# 2021-01-12_HALO_Main_Board.net
KiCad netlist of a schematic drawn in EAGLE
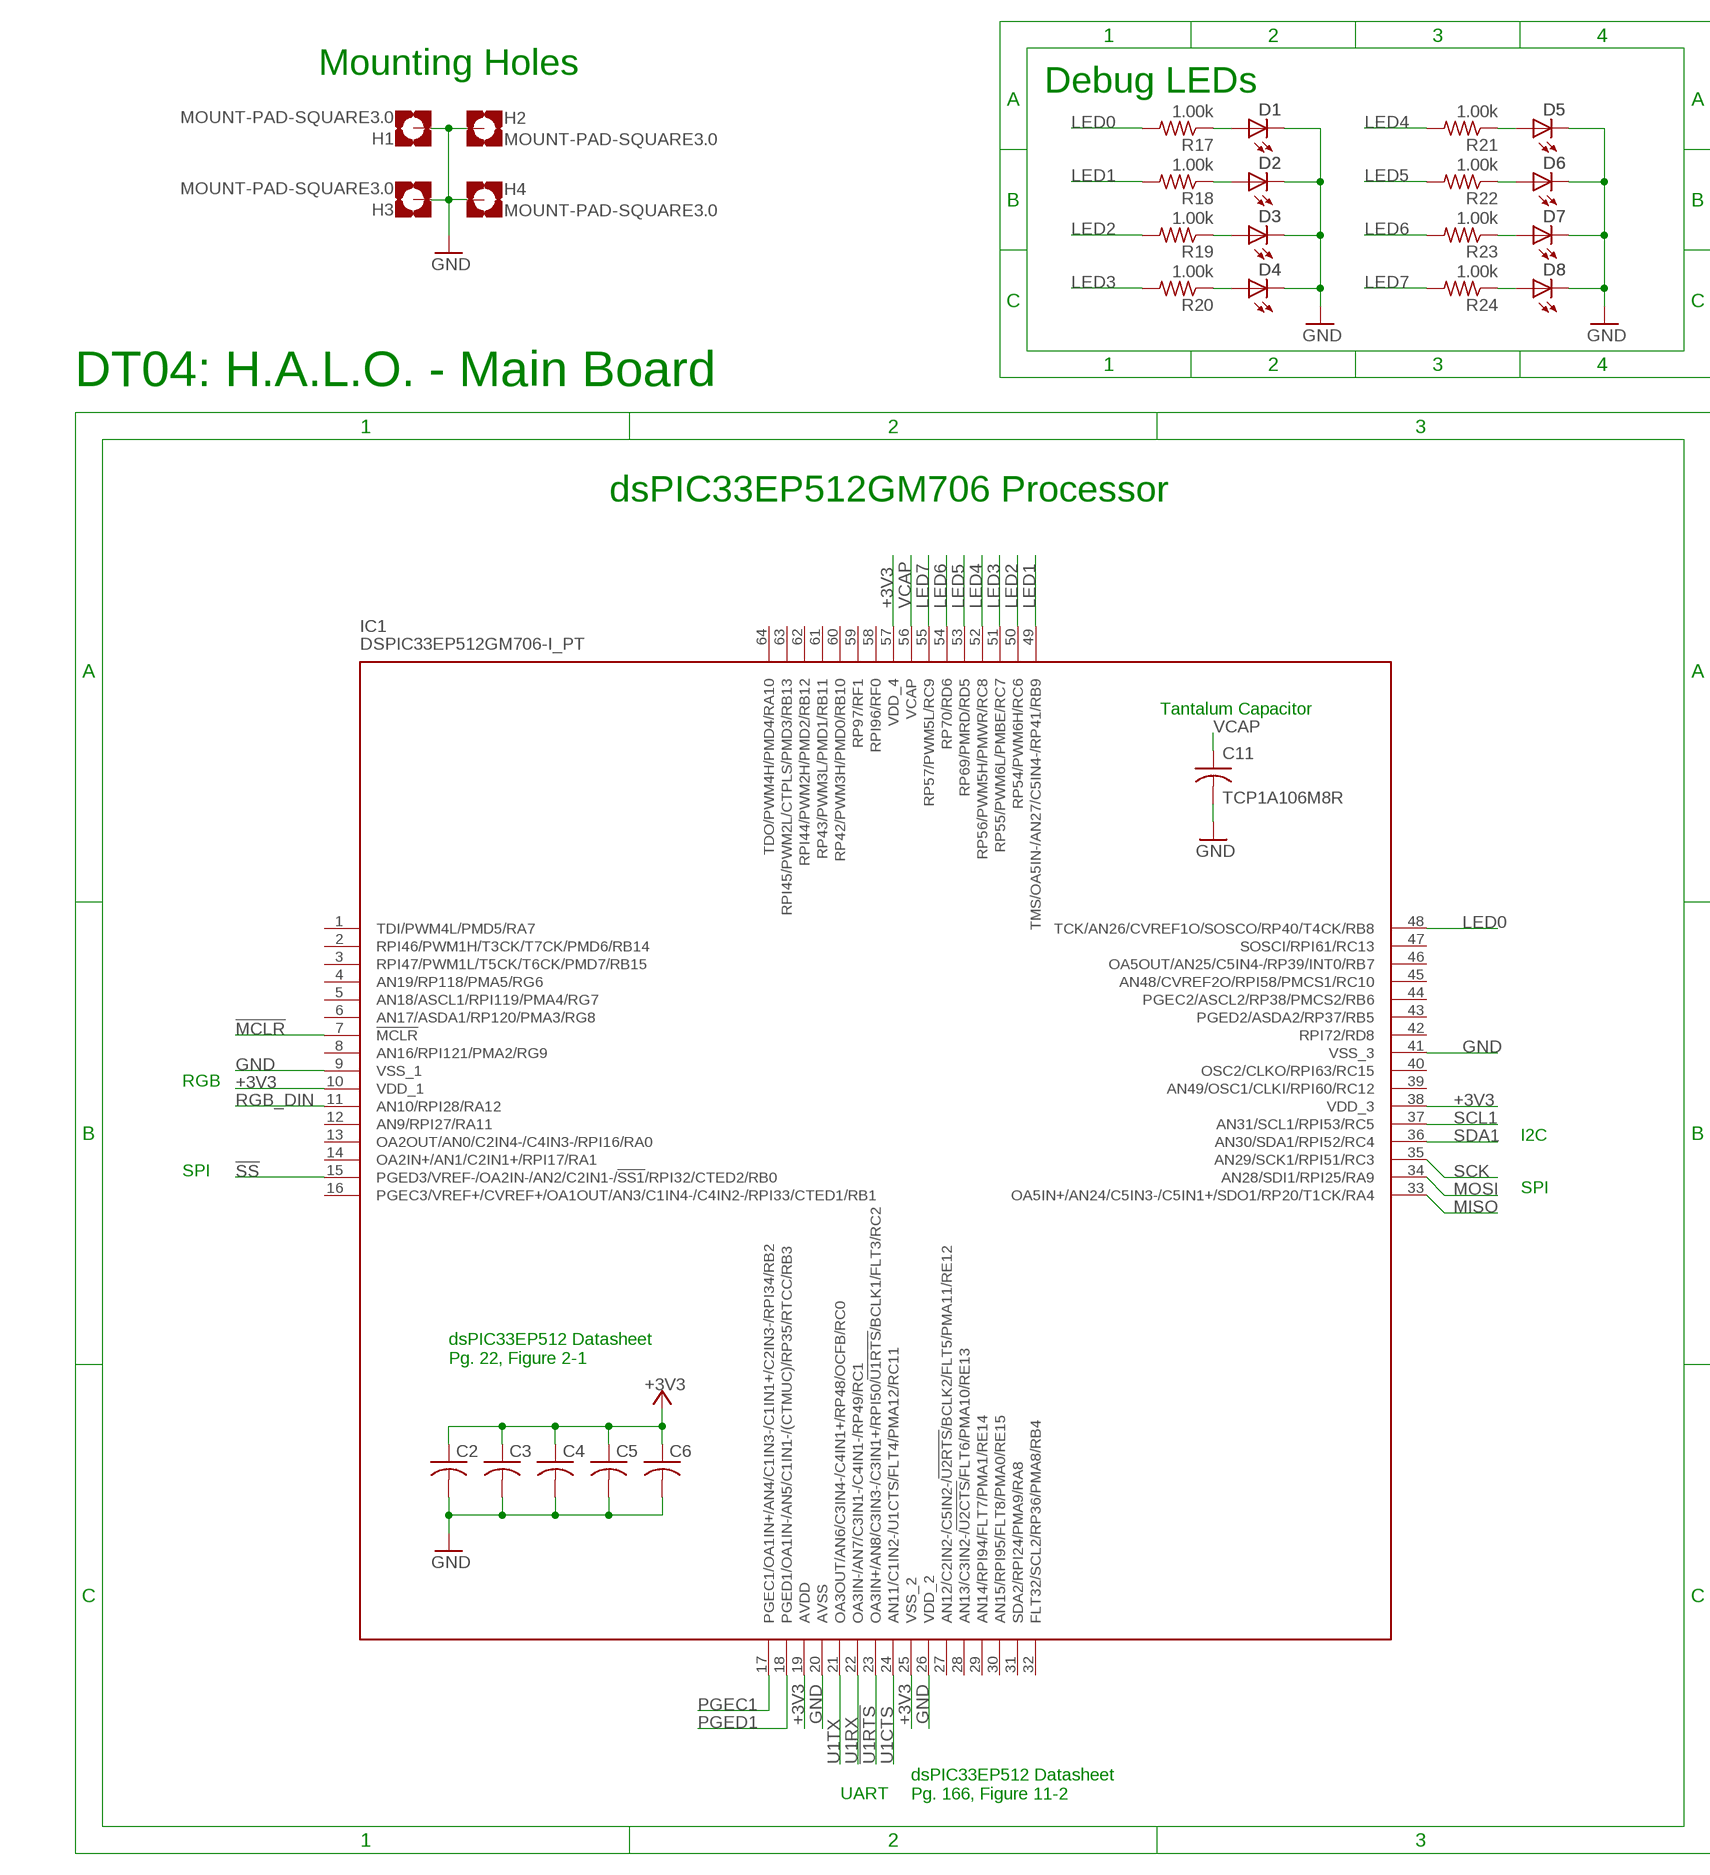
[diagram p0: schematic, sheet 1, part 1 of 2]
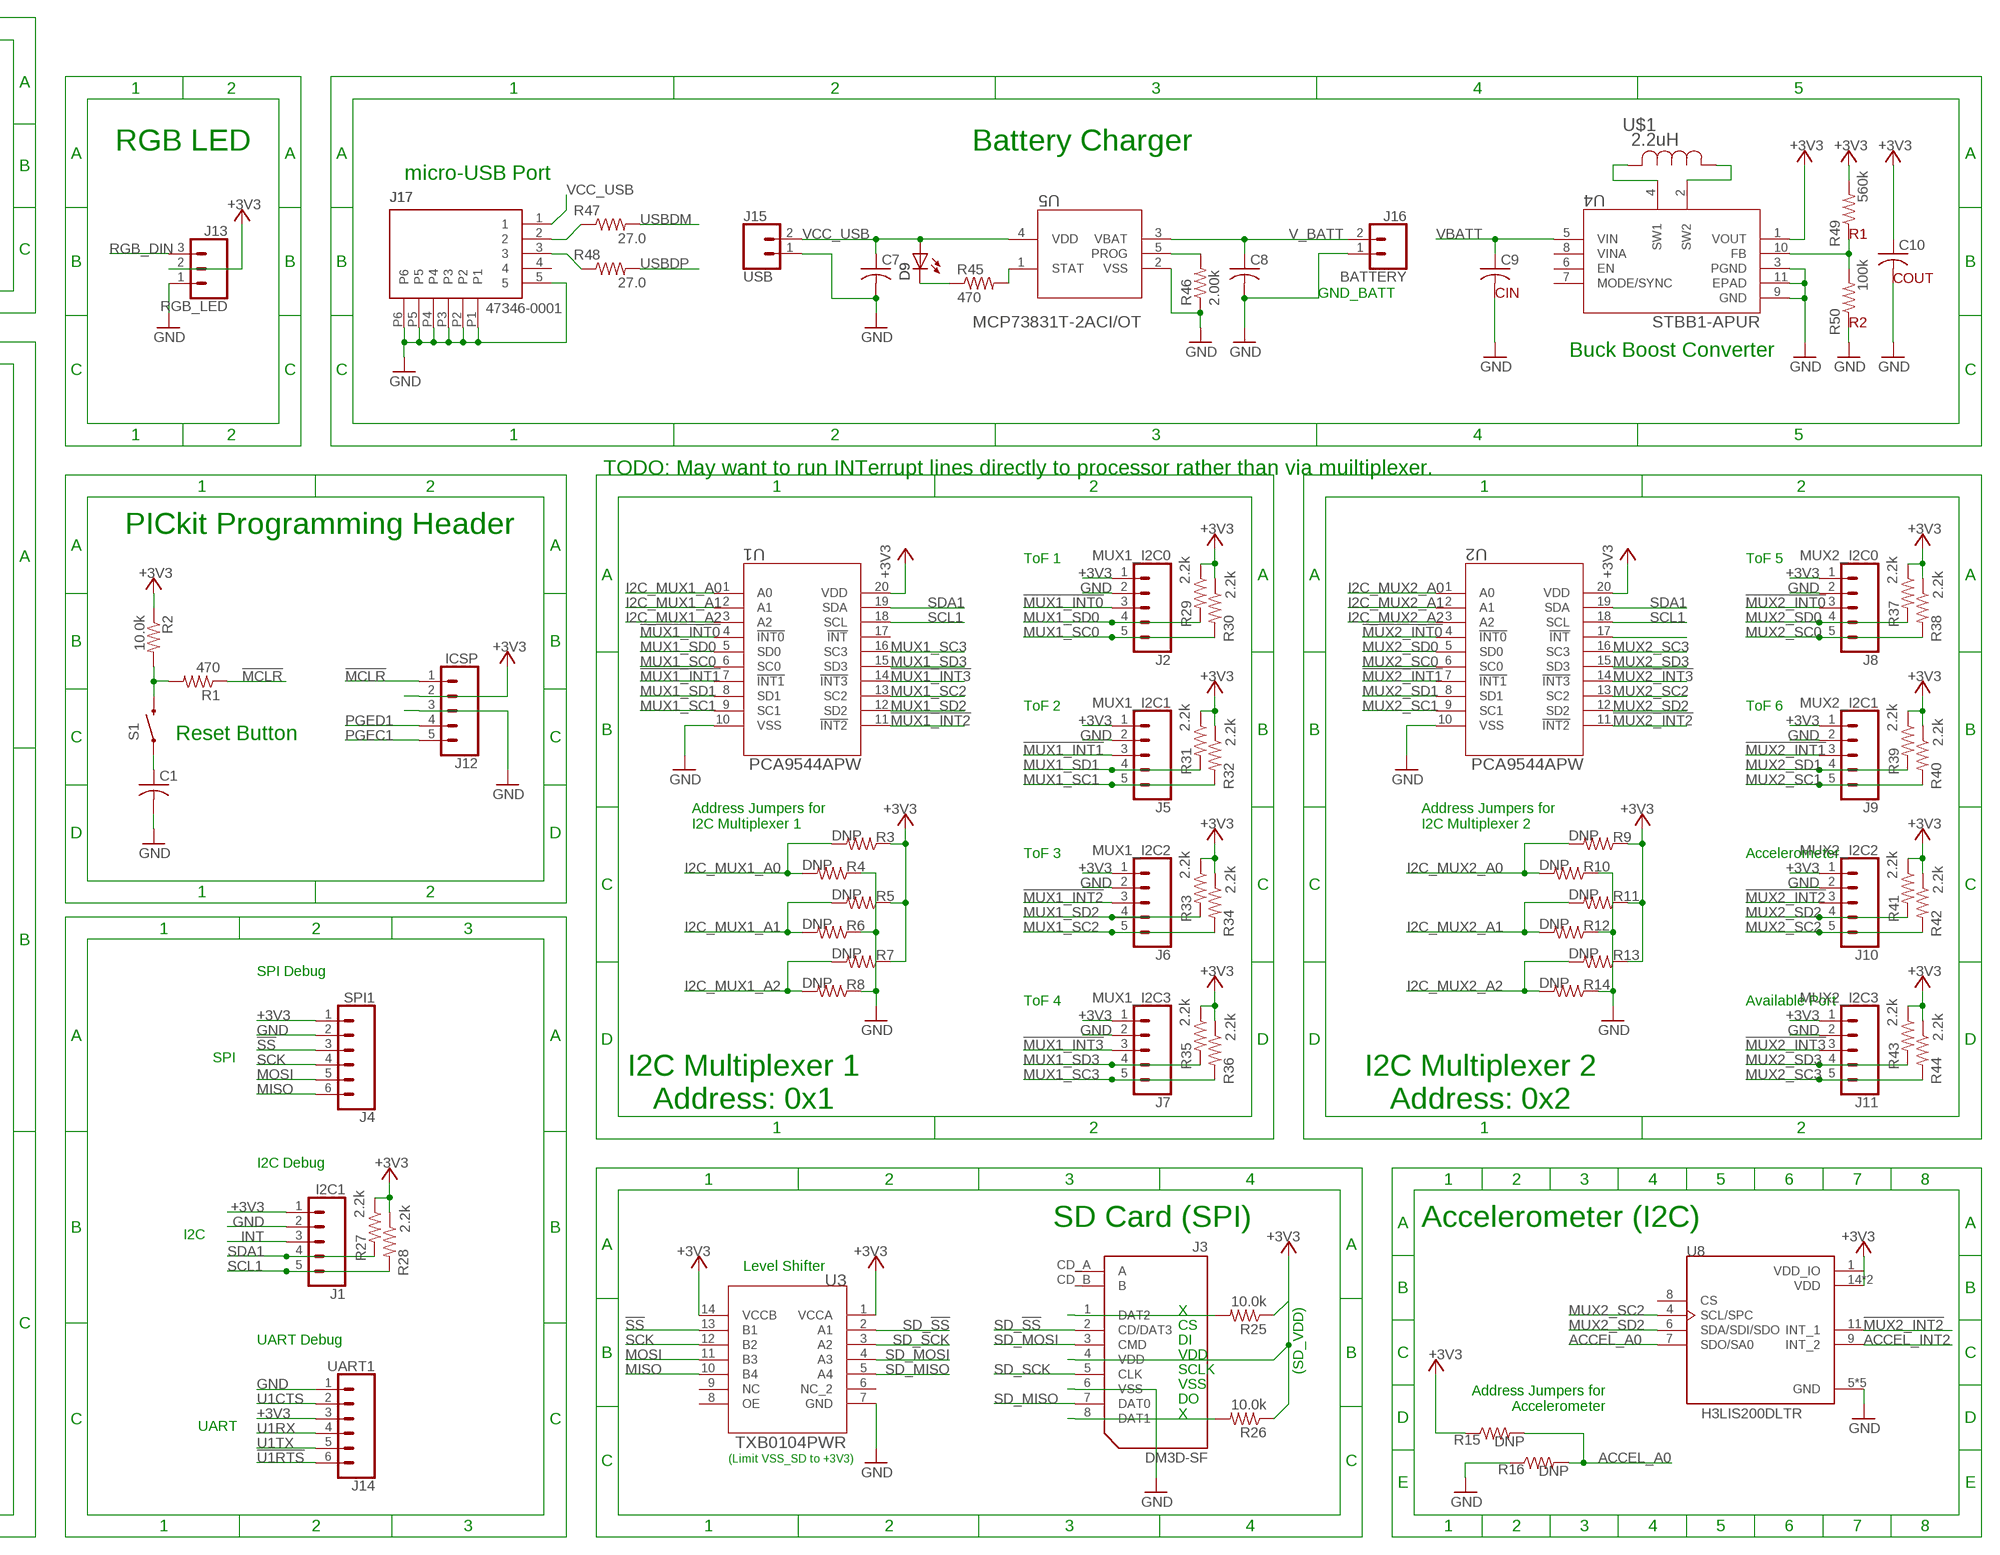
[diagram p1: schematic, sheet 1, part 2 of 2]

(export (version "E")
  (design (tool "Eeschema 10.0.6"))
  (components
    (comp (ref "C1")
      (value "0.1uF")
      (footprint "eagle-import:C0805")
      (libsource (lib "eagle-import") (part "C-USC0805"))
    )
    (comp (ref "C2")
      (value "0.1uF")
      (footprint "eagle-import:C0805")
      (libsource (lib "eagle-import") (part "C-USC0805"))
    )
    (comp (ref "C3")
      (value "0.1uF")
      (footprint "eagle-import:C0805")
      (libsource (lib "eagle-import") (part "C-USC0805"))
    )
    (comp (ref "C4")
      (value "0.1uF")
      (footprint "eagle-import:C0805")
      (libsource (lib "eagle-import") (part "C-USC0805"))
    )
    (comp (ref "C5")
      (value "0.1uF")
      (footprint "eagle-import:C0805")
      (libsource (lib "eagle-import") (part "C-USC0805"))
    )
    (comp (ref "C6")
      (value "0.1uF")
      (footprint "eagle-import:C0805")
      (libsource (lib "eagle-import") (part "C-USC0805"))
    )
    (comp (ref "C7")
      (value "4.7uF")
      (footprint "eagle-import:C0805")
      (libsource (lib "eagle-import") (part "C-USC0805"))
    )
    (comp (ref "C8")
      (value "4.7uF")
      (footprint "eagle-import:C0805")
      (libsource (lib "eagle-import") (part "C-USC0805"))
    )
    (comp (ref "C9")
      (value "10uF")
      (footprint "eagle-import:C0805")
      (libsource (lib "eagle-import") (part "C-USC0805"))
    )
    (comp (ref "C10")
      (value "22uF")
      (footprint "eagle-import:C0805")
      (libsource (lib "eagle-import") (part "C-USC0805"))
    )
    (comp (ref "C11")
      (value "TCP1A106M8R")
      (footprint "eagle-import:TCP_ROM")
      (libsource (lib "eagle-import") (part "TCP1A106M8R"))
    )
    (comp (ref "D1")
      (value "CHIP-LED0805")
      (footprint "eagle-import:CHIP-LED0805")
      (libsource (lib "eagle-import") (part "CHIP-LED0805"))
    )
    (comp (ref "D2")
      (value "CHIP-LED0805")
      (footprint "eagle-import:CHIP-LED0805")
      (libsource (lib "eagle-import") (part "CHIP-LED0805"))
    )
    (comp (ref "D3")
      (value "CHIP-LED0805")
      (footprint "eagle-import:CHIP-LED0805")
      (libsource (lib "eagle-import") (part "CHIP-LED0805"))
    )
    (comp (ref "D4")
      (value "CHIP-LED0805")
      (footprint "eagle-import:CHIP-LED0805")
      (libsource (lib "eagle-import") (part "CHIP-LED0805"))
    )
    (comp (ref "D5")
      (value "CHIP-LED0805")
      (footprint "eagle-import:CHIP-LED0805")
      (libsource (lib "eagle-import") (part "CHIP-LED0805"))
    )
    (comp (ref "D6")
      (value "CHIP-LED0805")
      (footprint "eagle-import:CHIP-LED0805")
      (libsource (lib "eagle-import") (part "CHIP-LED0805"))
    )
    (comp (ref "D7")
      (value "CHIP-LED0805")
      (footprint "eagle-import:CHIP-LED0805")
      (libsource (lib "eagle-import") (part "CHIP-LED0805"))
    )
    (comp (ref "D8")
      (value "CHIP-LED0805")
      (footprint "eagle-import:CHIP-LED0805")
      (libsource (lib "eagle-import") (part "CHIP-LED0805"))
    )
    (comp (ref "D9")
      (value "CHIP-LED0805")
      (footprint "eagle-import:CHIP-LED0805")
      (libsource (lib "eagle-import") (part "CHIP-LED0805"))
    )
    (comp (ref "H1")
      (value "MOUNT-PAD-SQUARE3.0")
      (footprint "eagle-import:3,0-PAD-SQUARE")
      (libsource (lib "eagle-import") (part "MOUNT-PAD-SQUARE3.0"))
    )
    (comp (ref "H2")
      (value "MOUNT-PAD-SQUARE3.0")
      (footprint "eagle-import:3,0-PAD-SQUARE")
      (libsource (lib "eagle-import") (part "MOUNT-PAD-SQUARE3.0"))
    )
    (comp (ref "H3")
      (value "MOUNT-PAD-SQUARE3.0")
      (footprint "eagle-import:3,0-PAD-SQUARE")
      (libsource (lib "eagle-import") (part "MOUNT-PAD-SQUARE3.0"))
    )
    (comp (ref "H4")
      (value "MOUNT-PAD-SQUARE3.0")
      (footprint "eagle-import:3,0-PAD-SQUARE")
      (libsource (lib "eagle-import") (part "MOUNT-PAD-SQUARE3.0"))
    )
    (comp (ref "IC1")
      (value "DSPIC33EP512GM706-I_PT")
      (footprint "eagle-import:QFP50P1200X1200X120-64N")
      (fields
        (field (name "ARROW_PART_NUMBER") "DSPIC33EP512GM706-I/PT")
        (field (name "MOUSER_PART_NUMBER") "579-512GM706-I/PT")
      )
      (libsource (lib "eagle-import") (part "DSPIC33EP512GM706-I_PT"))
    )
    (comp (ref "J1")
      (value "I2C1")
      (footprint "eagle-import:1X05")
      (libsource (lib "eagle-import") (part "CONN_05"))
    )
    (comp (ref "J2")
      (value "MUX1_I2C0")
      (footprint "eagle-import:1X05")
      (libsource (lib "eagle-import") (part "CONN_05"))
    )
    (comp (ref "J3")
      (value "DM3D-SF")
      (footprint "eagle-import:SD_CARD")
      (fields (field (name "PARTNO") "AS-ITM-00047"))
      (libsource (lib "eagle-import") (part "AS-ITM-00047"))
    )
    (comp (ref "J4")
      (value "SPI1")
      (footprint "eagle-import:1X06")
      (libsource (lib "eagle-import") (part "CONN_06SILK_FEMALE_PTH"))
    )
    (comp (ref "J5")
      (value "MUX1_I2C1")
      (footprint "eagle-import:1X05")
      (libsource (lib "eagle-import") (part "CONN_05"))
    )
    (comp (ref "J6")
      (value "MUX1_I2C2")
      (footprint "eagle-import:1X05")
      (libsource (lib "eagle-import") (part "CONN_05"))
    )
    (comp (ref "J7")
      (value "MUX1_I2C3")
      (footprint "eagle-import:1X05")
      (libsource (lib "eagle-import") (part "CONN_05"))
    )
    (comp (ref "J8")
      (value "MUX2_I2C0")
      (footprint "eagle-import:1X05")
      (libsource (lib "eagle-import") (part "CONN_05"))
    )
    (comp (ref "J9")
      (value "MUX2_I2C1")
      (footprint "eagle-import:1X05")
      (libsource (lib "eagle-import") (part "CONN_05"))
    )
    (comp (ref "J10")
      (value "MUX2_I2C2")
      (footprint "eagle-import:1X05")
      (libsource (lib "eagle-import") (part "CONN_05"))
    )
    (comp (ref "J11")
      (value "MUX2_I2C3")
      (footprint "eagle-import:1X05")
      (libsource (lib "eagle-import") (part "CONN_05"))
    )
    (comp (ref "J12")
      (value "ICSP")
      (footprint "eagle-import:1X05")
      (libsource (lib "eagle-import") (part "CONN_05"))
    )
    (comp (ref "J13")
      (value "RGB_LED")
      (footprint "eagle-import:1X03_LOCK")
      (libsource (lib "eagle-import") (part "CONN_03LOCK"))
    )
    (comp (ref "J14")
      (value "UART1")
      (footprint "eagle-import:1X06")
      (libsource (lib "eagle-import") (part "CONN_06SILK_FEMALE_PTH"))
    )
    (comp (ref "J15")
      (value "USB")
      (footprint "eagle-import:1X02")
      (libsource (lib "eagle-import") (part "CONN_02"))
    )
    (comp (ref "J16")
      (value "BATTERY")
      (footprint "eagle-import:1X02")
      (libsource (lib "eagle-import") (part "CONN_02"))
    )
    (comp (ref "J17")
      (value "47346-0001")
      (footprint "eagle-import:MICRO_USB")
      (fields (field (name "PARTNO") "AS-ITM-00021") (field (name "PARTNO_1") "AS-ITM-00021"))
      (libsource (lib "eagle-import") (part "AS-ITM-00021"))
    )
    (comp (ref "R1")
      (value "470")
      (footprint "eagle-import:R0805")
      (libsource (lib "eagle-import") (part "R-US_R0805"))
    )
    (comp (ref "R2")
      (value "10.0k")
      (footprint "eagle-import:R0805")
      (libsource (lib "eagle-import") (part "R-US_R0805"))
    )
    (comp (ref "R3")
      (value "DNP")
      (footprint "eagle-import:R0805")
      (libsource (lib "eagle-import") (part "R-US_R0805"))
    )
    (comp (ref "R4")
      (value "DNP")
      (footprint "eagle-import:R0805")
      (libsource (lib "eagle-import") (part "R-US_R0805"))
    )
    (comp (ref "R5")
      (value "DNP")
      (footprint "eagle-import:R0805")
      (libsource (lib "eagle-import") (part "R-US_R0805"))
    )
    (comp (ref "R6")
      (value "DNP")
      (footprint "eagle-import:R0805")
      (libsource (lib "eagle-import") (part "R-US_R0805"))
    )
    (comp (ref "R7")
      (value "DNP")
      (footprint "eagle-import:R0805")
      (libsource (lib "eagle-import") (part "R-US_R0805"))
    )
    (comp (ref "R8")
      (value "DNP")
      (footprint "eagle-import:R0805")
      (libsource (lib "eagle-import") (part "R-US_R0805"))
    )
    (comp (ref "R9")
      (value "DNP")
      (footprint "eagle-import:R0805")
      (libsource (lib "eagle-import") (part "R-US_R0805"))
    )
    (comp (ref "R10")
      (value "DNP")
      (footprint "eagle-import:R0805")
      (libsource (lib "eagle-import") (part "R-US_R0805"))
    )
    (comp (ref "R11")
      (value "DNP")
      (footprint "eagle-import:R0805")
      (libsource (lib "eagle-import") (part "R-US_R0805"))
    )
    (comp (ref "R12")
      (value "DNP")
      (footprint "eagle-import:R0805")
      (libsource (lib "eagle-import") (part "R-US_R0805"))
    )
    (comp (ref "R13")
      (value "DNP")
      (footprint "eagle-import:R0805")
      (libsource (lib "eagle-import") (part "R-US_R0805"))
    )
    (comp (ref "R14")
      (value "DNP")
      (footprint "eagle-import:R0805")
      (libsource (lib "eagle-import") (part "R-US_R0805"))
    )
    (comp (ref "R15")
      (value "DNP")
      (footprint "eagle-import:R0805")
      (libsource (lib "eagle-import") (part "R-US_R0805"))
    )
    (comp (ref "R16")
      (value "DNP")
      (footprint "eagle-import:R0805")
      (libsource (lib "eagle-import") (part "R-US_R0805"))
    )
    (comp (ref "R17")
      (value "1.00k")
      (footprint "eagle-import:R0805")
      (libsource (lib "eagle-import") (part "R-US_R0805"))
    )
    (comp (ref "R18")
      (value "1.00k")
      (footprint "eagle-import:R0805")
      (libsource (lib "eagle-import") (part "R-US_R0805"))
    )
    (comp (ref "R19")
      (value "1.00k")
      (footprint "eagle-import:R0805")
      (libsource (lib "eagle-import") (part "R-US_R0805"))
    )
    (comp (ref "R20")
      (value "1.00k")
      (footprint "eagle-import:R0805")
      (libsource (lib "eagle-import") (part "R-US_R0805"))
    )
    (comp (ref "R21")
      (value "1.00k")
      (footprint "eagle-import:R0805")
      (libsource (lib "eagle-import") (part "R-US_R0805"))
    )
    (comp (ref "R22")
      (value "1.00k")
      (footprint "eagle-import:R0805")
      (libsource (lib "eagle-import") (part "R-US_R0805"))
    )
    (comp (ref "R23")
      (value "1.00k")
      (footprint "eagle-import:R0805")
      (libsource (lib "eagle-import") (part "R-US_R0805"))
    )
    (comp (ref "R24")
      (value "1.00k")
      (footprint "eagle-import:R0805")
      (libsource (lib "eagle-import") (part "R-US_R0805"))
    )
    (comp (ref "R25")
      (value "10.0k")
      (footprint "eagle-import:R0805")
      (libsource (lib "eagle-import") (part "R-US_R0805"))
    )
    (comp (ref "R26")
      (value "10.0k")
      (footprint "eagle-import:R0805")
      (libsource (lib "eagle-import") (part "R-US_R0805"))
    )
    (comp (ref "R27")
      (value "2.2k")
      (footprint "eagle-import:R0805")
      (libsource (lib "eagle-import") (part "R-US_R0805"))
    )
    (comp (ref "R28")
      (value "2.2k")
      (footprint "eagle-import:R0805")
      (libsource (lib "eagle-import") (part "R-US_R0805"))
    )
    (comp (ref "R29")
      (value "2.2k")
      (footprint "eagle-import:R0805")
      (libsource (lib "eagle-import") (part "R-US_R0805"))
    )
    (comp (ref "R30")
      (value "2.2k")
      (footprint "eagle-import:R0805")
      (libsource (lib "eagle-import") (part "R-US_R0805"))
    )
    (comp (ref "R31")
      (value "2.2k")
      (footprint "eagle-import:R0805")
      (libsource (lib "eagle-import") (part "R-US_R0805"))
    )
    (comp (ref "R32")
      (value "2.2k")
      (footprint "eagle-import:R0805")
      (libsource (lib "eagle-import") (part "R-US_R0805"))
    )
    (comp (ref "R33")
      (value "2.2k")
      (footprint "eagle-import:R0805")
      (libsource (lib "eagle-import") (part "R-US_R0805"))
    )
    (comp (ref "R34")
      (value "2.2k")
      (footprint "eagle-import:R0805")
      (libsource (lib "eagle-import") (part "R-US_R0805"))
    )
    (comp (ref "R35")
      (value "2.2k")
      (footprint "eagle-import:R0805")
      (libsource (lib "eagle-import") (part "R-US_R0805"))
    )
    (comp (ref "R36")
      (value "2.2k")
      (footprint "eagle-import:R0805")
      (libsource (lib "eagle-import") (part "R-US_R0805"))
    )
    (comp (ref "R37")
      (value "2.2k")
      (footprint "eagle-import:R0805")
      (libsource (lib "eagle-import") (part "R-US_R0805"))
    )
    (comp (ref "R38")
      (value "2.2k")
      (footprint "eagle-import:R0805")
      (libsource (lib "eagle-import") (part "R-US_R0805"))
    )
    (comp (ref "R39")
      (value "2.2k")
      (footprint "eagle-import:R0805")
      (libsource (lib "eagle-import") (part "R-US_R0805"))
    )
    (comp (ref "R40")
      (value "2.2k")
      (footprint "eagle-import:R0805")
      (libsource (lib "eagle-import") (part "R-US_R0805"))
    )
    (comp (ref "R41")
      (value "2.2k")
      (footprint "eagle-import:R0805")
      (libsource (lib "eagle-import") (part "R-US_R0805"))
    )
    (comp (ref "R42")
      (value "2.2k")
      (footprint "eagle-import:R0805")
      (libsource (lib "eagle-import") (part "R-US_R0805"))
    )
    (comp (ref "R43")
      (value "2.2k")
      (footprint "eagle-import:R0805")
      (libsource (lib "eagle-import") (part "R-US_R0805"))
    )
    (comp (ref "R44")
      (value "2.2k")
      (footprint "eagle-import:R0805")
      (libsource (lib "eagle-import") (part "R-US_R0805"))
    )
    (comp (ref "R45")
      (value "470")
      (footprint "eagle-import:R0805")
      (libsource (lib "eagle-import") (part "R-US_R0805"))
    )
    (comp (ref "R46")
      (value "2.00k")
      (footprint "eagle-import:R0805")
      (libsource (lib "eagle-import") (part "R-US_R0805"))
    )
    (comp (ref "R47")
      (value "27.0")
      (footprint "eagle-import:R0805")
      (libsource (lib "eagle-import") (part "R-US_R0805"))
    )
    (comp (ref "R48")
      (value "27.0")
      (footprint "eagle-import:R0805")
      (libsource (lib "eagle-import") (part "R-US_R0805"))
    )
    (comp (ref "R49")
      (value "560k")
      (footprint "eagle-import:R0805")
      (libsource (lib "eagle-import") (part "R-US_R0805"))
    )
    (comp (ref "R50")
      (value "100k")
      (footprint "eagle-import:R0805")
      (libsource (lib "eagle-import") (part "R-US_R0805"))
    )
    (comp (ref "S1")
      (value "SWITCH-MOMENTARY-2SMD-4")
      (footprint "eagle-import:TACTILE_SWITCH_TALL")
      (libsource (lib "eagle-import") (part "SWITCH-MOMENTARY-2SMD-4"))
    )
    (comp (ref "U$1")
      (value "2.2uH")
      (footprint "eagle-import:IND_4028_TDK")
      (libsource (lib "eagle-import") (part "IND"))
    )
    (comp (ref "U1")
      (value "PCA9544APW")
      (footprint "eagle-import:SOT360-1_NXP")
      (libsource (lib "eagle-import") (part "PCA9544APW"))
    )
    (comp (ref "U2")
      (value "PCA9544APW")
      (footprint "eagle-import:SOT360-1_NXP")
      (libsource (lib "eagle-import") (part "PCA9544APW"))
    )
    (comp (ref "U3")
      (value "TXB0104PWR")
      (footprint "eagle-import:PW14")
      (fields
        (field (name "GENERIC_PART_NUMBER") "TXB0104")
        (field (name "MANUFACTURER") "Texas Instruments")
      )
      (libsource (lib "eagle-import") (part "TXB0104PWR"))
    )
    (comp (ref "U4")
      (value "STBB1-APUR")
      (footprint "eagle-import:SON_B1-APUR_STM")
      (libsource (lib "eagle-import") (part "STBB1-APUR"))
    )
    (comp (ref "U5")
      (value "MCP73831T-2ACI/OT")
      (footprint "eagle-import:SOT-23-5_MC_MCH")
      (libsource (lib "eagle-import") (part "MCP73831T-2ACI/OT"))
    )
    (comp (ref "U8")
      (value "H3LIS200DLTR")
      (footprint "eagle-import:PQFN50P300X300X100-16N")
      (fields (field (name "DIGI-KEY_PART_NUMBER") "497-15698-1-ND") (field (name "MF") "STMicroelectronics"))
      (libsource (lib "eagle-import") (part "H3LIS200DLTR"))
    )
  )
  (nets
    (net (code "1") (name "+3V3") (class "Default")
      (node (ref "C10") (pin "1") (pinfunction "1_1") (pintype "passive"))
      (node (ref "C2") (pin "1") (pinfunction "1_1") (pintype "passive"))
      (node (ref "C3") (pin "1") (pinfunction "1_1") (pintype "passive"))
      (node (ref "C4") (pin "1") (pinfunction "1_1") (pintype "passive"))
      (node (ref "C5") (pin "1") (pinfunction "1_1") (pintype "passive"))
      (node (ref "C6") (pin "1") (pinfunction "1_1") (pintype "passive"))
      (node (ref "IC1") (pin "10") (pinfunction "VDD_1_10") (pintype "bidirectional"))
      (node (ref "IC1") (pin "19") (pinfunction "AVDD_19") (pintype "bidirectional"))
      (node (ref "IC1") (pin "25") (pinfunction "VSS_2_25") (pintype "bidirectional"))
      (node (ref "IC1") (pin "38") (pinfunction "VDD_3_38") (pintype "bidirectional"))
      (node (ref "IC1") (pin "57") (pinfunction "VDD_4_57") (pintype "bidirectional"))
      (node (ref "J1") (pin "1") (pinfunction "1_1") (pintype "passive"))
      (node (ref "J10") (pin "1") (pinfunction "1_1") (pintype "passive"))
      (node (ref "J11") (pin "1") (pinfunction "1_1") (pintype "passive"))
      (node (ref "J12") (pin "2") (pinfunction "2_2") (pintype "passive"))
      (node (ref "J13") (pin "2") (pinfunction "2_2") (pintype "passive"))
      (node (ref "J14") (pin "3") (pinfunction "3_3") (pintype "passive"))
      (node (ref "J2") (pin "1") (pinfunction "1_1") (pintype "passive"))
      (node (ref "J3") (pin "4") (pinfunction "VDD_4") (pintype "bidirectional"))
      (node (ref "J4") (pin "1") (pinfunction "1_1") (pintype "passive"))
      (node (ref "J5") (pin "1") (pinfunction "1_1") (pintype "passive"))
      (node (ref "J6") (pin "1") (pinfunction "1_1") (pintype "passive"))
      (node (ref "J7") (pin "1") (pinfunction "1_1") (pintype "passive"))
      (node (ref "J8") (pin "1") (pinfunction "1_1") (pintype "passive"))
      (node (ref "J9") (pin "1") (pinfunction "1_1") (pintype "passive"))
      (node (ref "R11") (pin "1") (pinfunction "1_1") (pintype "passive"))
      (node (ref "R13") (pin "1") (pinfunction "1_1") (pintype "passive"))
      (node (ref "R15") (pin "1") (pinfunction "1_1") (pintype "passive"))
      (node (ref "R2") (pin "1") (pinfunction "1_1") (pintype "passive"))
      (node (ref "R25") (pin "1") (pinfunction "1_1") (pintype "passive"))
      (node (ref "R26") (pin "1") (pinfunction "1_1") (pintype "passive"))
      (node (ref "R27") (pin "1") (pinfunction "1_1") (pintype "passive"))
      (node (ref "R28") (pin "1") (pinfunction "1_1") (pintype "passive"))
      (node (ref "R29") (pin "1") (pinfunction "1_1") (pintype "passive"))
      (node (ref "R3") (pin "1") (pinfunction "1_1") (pintype "passive"))
      (node (ref "R30") (pin "1") (pinfunction "1_1") (pintype "passive"))
      (node (ref "R31") (pin "1") (pinfunction "1_1") (pintype "passive"))
      (node (ref "R32") (pin "1") (pinfunction "1_1") (pintype "passive"))
      (node (ref "R33") (pin "1") (pinfunction "1_1") (pintype "passive"))
      (node (ref "R34") (pin "1") (pinfunction "1_1") (pintype "passive"))
      (node (ref "R35") (pin "1") (pinfunction "1_1") (pintype "passive"))
      (node (ref "R36") (pin "1") (pinfunction "1_1") (pintype "passive"))
      (node (ref "R37") (pin "1") (pinfunction "1_1") (pintype "passive"))
      (node (ref "R38") (pin "1") (pinfunction "1_1") (pintype "passive"))
      (node (ref "R39") (pin "1") (pinfunction "1_1") (pintype "passive"))
      (node (ref "R40") (pin "1") (pinfunction "1_1") (pintype "passive"))
      (node (ref "R41") (pin "1") (pinfunction "1_1") (pintype "passive"))
      (node (ref "R42") (pin "1") (pinfunction "1_1") (pintype "passive"))
      (node (ref "R43") (pin "1") (pinfunction "1_1") (pintype "passive"))
      (node (ref "R44") (pin "1") (pinfunction "1_1") (pintype "passive"))
      (node (ref "R49") (pin "2") (pinfunction "2_2") (pintype "passive"))
      (node (ref "R5") (pin "1") (pinfunction "1_1") (pintype "passive"))
      (node (ref "R7") (pin "1") (pinfunction "1_1") (pintype "passive"))
      (node (ref "R9") (pin "1") (pinfunction "1_1") (pintype "passive"))
      (node (ref "U1") (pin "20") (pinfunction "VDD_20") (pintype "passive"))
      (node (ref "U2") (pin "20") (pinfunction "VDD_20") (pintype "passive"))
      (node (ref "U3") (pin "1") (pinfunction "VCCA_1") (pintype "power_in"))
      (node (ref "U3") (pin "14") (pinfunction "VCCB_14") (pintype "power_in"))
      (node (ref "U4") (pin "1") (pinfunction "VOUT_1") (pintype "power_in"))
      (node (ref "U8") (pin "1") (pinfunction "VDD_IO_1") (pintype "power_in"))
      (node (ref "U8") (pin "14") (pinfunction "VDD_14") (pintype "power_in"))
      (node (ref "U8") (pin "15") (pinfunction "VDD_15") (pintype "power_in"))
    )
    (net (code "2") (name "/ACCEL_A0") (class "Default")
      (node (ref "R15") (pin "2") (pinfunction "2_2") (pintype "passive"))
      (node (ref "R16") (pin "2") (pinfunction "2_2") (pintype "passive"))
      (node (ref "U8") (pin "7") (pinfunction "SDO/SA0_7") (pintype "output"))
    )
    (net (code "3") (name "/ACCEL_INT2") (class "Default")
      (node (ref "U8") (pin "9") (pinfunction "INT_2_9") (pintype "output"))
    )
    (net (code "4") (name "/I2C_MUX1_A0") (class "Default")
      (node (ref "R3") (pin "2") (pinfunction "2_2") (pintype "passive"))
      (node (ref "R4") (pin "2") (pinfunction "2_2") (pintype "passive"))
      (node (ref "U1") (pin "1") (pinfunction "A0_1") (pintype "passive"))
    )
    (net (code "5") (name "/I2C_MUX1_A1") (class "Default")
      (node (ref "R5") (pin "2") (pinfunction "2_2") (pintype "passive"))
      (node (ref "R6") (pin "2") (pinfunction "2_2") (pintype "passive"))
      (node (ref "U1") (pin "2") (pinfunction "A1_2") (pintype "passive"))
    )
    (net (code "6") (name "/I2C_MUX1_A2") (class "Default")
      (node (ref "R7") (pin "2") (pinfunction "2_2") (pintype "passive"))
      (node (ref "R8") (pin "2") (pinfunction "2_2") (pintype "passive"))
      (node (ref "U1") (pin "3") (pinfunction "A2_3") (pintype "passive"))
    )
    (net (code "7") (name "/I2C_MUX2_A0") (class "Default")
      (node (ref "R10") (pin "2") (pinfunction "2_2") (pintype "passive"))
      (node (ref "R9") (pin "2") (pinfunction "2_2") (pintype "passive"))
      (node (ref "U2") (pin "1") (pinfunction "A0_1") (pintype "passive"))
    )
    (net (code "8") (name "/I2C_MUX2_A1") (class "Default")
      (node (ref "R11") (pin "2") (pinfunction "2_2") (pintype "passive"))
      (node (ref "R12") (pin "2") (pinfunction "2_2") (pintype "passive"))
      (node (ref "U2") (pin "2") (pinfunction "A1_2") (pintype "passive"))
    )
    (net (code "9") (name "/I2C_MUX2_A2") (class "Default")
      (node (ref "R13") (pin "2") (pinfunction "2_2") (pintype "passive"))
      (node (ref "R14") (pin "2") (pinfunction "2_2") (pintype "passive"))
      (node (ref "U2") (pin "3") (pinfunction "A2_3") (pintype "passive"))
    )
    (net (code "10") (name "/INT") (class "Default")
      (node (ref "J1") (pin "3") (pinfunction "3_3") (pintype "passive"))
    )
    (net (code "11") (name "/LED0") (class "Default")
      (node (ref "IC1") (pin "48") (pinfunction "TCK/AN26/CVREF1O/SOSCO/RP40/T4CK/RB8_48") (pintype "bidirectional"))
      (node (ref "R17") (pin "2") (pinfunction "2_2") (pintype "passive"))
    )
    (net (code "12") (name "/LED1") (class "Default")
      (node (ref "IC1") (pin "49") (pinfunction "TMS/OA5IN-/AN27/C5IN4-/RP41/RB9_49") (pintype "bidirectional"))
      (node (ref "R18") (pin "2") (pinfunction "2_2") (pintype "passive"))
    )
    (net (code "13") (name "/LED2") (class "Default")
      (node (ref "IC1") (pin "50") (pinfunction "RP54/PWM6H/RC6_50") (pintype "bidirectional"))
      (node (ref "R19") (pin "2") (pinfunction "2_2") (pintype "passive"))
    )
    (net (code "14") (name "/LED3") (class "Default")
      (node (ref "IC1") (pin "51") (pinfunction "RP55/PWM6L/PMBE/RC7_51") (pintype "bidirectional"))
      (node (ref "R20") (pin "2") (pinfunction "2_2") (pintype "passive"))
    )
    (net (code "15") (name "/LED4") (class "Default")
      (node (ref "IC1") (pin "52") (pinfunction "RP56/PWM5H/PMWR/RC8_52") (pintype "bidirectional"))
      (node (ref "R21") (pin "2") (pinfunction "2_2") (pintype "passive"))
    )
    (net (code "16") (name "/LED5") (class "Default")
      (node (ref "IC1") (pin "53") (pinfunction "RP69/PMRD/RD5_53") (pintype "bidirectional"))
      (node (ref "R22") (pin "2") (pinfunction "2_2") (pintype "passive"))
    )
    (net (code "17") (name "/LED6") (class "Default")
      (node (ref "IC1") (pin "54") (pinfunction "RP70/RD6_54") (pintype "bidirectional"))
      (node (ref "R23") (pin "2") (pinfunction "2_2") (pintype "passive"))
    )
    (net (code "18") (name "/LED7") (class "Default")
      (node (ref "IC1") (pin "55") (pinfunction "RP57/PWM5L/RC9_55") (pintype "bidirectional"))
      (node (ref "R24") (pin "2") (pinfunction "2_2") (pintype "passive"))
    )
    (net (code "19") (name "/MISO") (class "Default")
      (node (ref "IC1") (pin "33") (pinfunction "OA5IN+/AN24/C5IN3-/C5IN1+/SDO1/RP20/T1CK/RA4_33") (pintype "bidirectional"))
      (node (ref "J4") (pin "6") (pinfunction "6_6") (pintype "passive"))
      (node (ref "U3") (pin "10") (pinfunction "B4_10") (pintype "bidirectional"))
    )
    (net (code "20") (name "/MOSI") (class "Default")
      (node (ref "IC1") (pin "34") (pinfunction "AN28/SDI1/RPI25/RA9_34") (pintype "bidirectional"))
      (node (ref "J4") (pin "5") (pinfunction "5_5") (pintype "passive"))
      (node (ref "U3") (pin "11") (pinfunction "B3_11") (pintype "bidirectional"))
    )
    (net (code "21") (name "/MUX1_SC0") (class "Default")
      (node (ref "J2") (pin "5") (pinfunction "5_5") (pintype "passive"))
      (node (ref "R30") (pin "2") (pinfunction "2_2") (pintype "passive"))
      (node (ref "U1") (pin "6") (pinfunction "SC0_6") (pintype "passive"))
    )
    (net (code "22") (name "/MUX1_SC1") (class "Default")
      (node (ref "J5") (pin "5") (pinfunction "5_5") (pintype "passive"))
      (node (ref "R32") (pin "2") (pinfunction "2_2") (pintype "passive"))
      (node (ref "U1") (pin "9") (pinfunction "SC1_9") (pintype "passive"))
    )
    (net (code "23") (name "/MUX1_SC2") (class "Default")
      (node (ref "J6") (pin "5") (pinfunction "5_5") (pintype "passive"))
      (node (ref "R34") (pin "2") (pinfunction "2_2") (pintype "passive"))
      (node (ref "U1") (pin "13") (pinfunction "SC2_13") (pintype "passive"))
    )
    (net (code "24") (name "/MUX1_SC3") (class "Default")
      (node (ref "J7") (pin "5") (pinfunction "5_5") (pintype "passive"))
      (node (ref "R36") (pin "2") (pinfunction "2_2") (pintype "passive"))
      (node (ref "U1") (pin "16") (pinfunction "SC3_16") (pintype "passive"))
    )
    (net (code "25") (name "/MUX1_SD0") (class "Default")
      (node (ref "J2") (pin "4") (pinfunction "4_4") (pintype "passive"))
      (node (ref "R29") (pin "2") (pinfunction "2_2") (pintype "passive"))
      (node (ref "U1") (pin "5") (pinfunction "SD0_5") (pintype "passive"))
    )
    (net (code "26") (name "/MUX1_SD1") (class "Default")
      (node (ref "J5") (pin "4") (pinfunction "4_4") (pintype "passive"))
      (node (ref "R31") (pin "2") (pinfunction "2_2") (pintype "passive"))
      (node (ref "U1") (pin "8") (pinfunction "SD1_8") (pintype "passive"))
    )
    (net (code "27") (name "/MUX1_SD2") (class "Default")
      (node (ref "J6") (pin "4") (pinfunction "4_4") (pintype "passive"))
      (node (ref "R33") (pin "2") (pinfunction "2_2") (pintype "passive"))
      (node (ref "U1") (pin "12") (pinfunction "SD2_12") (pintype "passive"))
    )
    (net (code "28") (name "/MUX1_SD3") (class "Default")
      (node (ref "J7") (pin "4") (pinfunction "4_4") (pintype "passive"))
      (node (ref "R35") (pin "2") (pinfunction "2_2") (pintype "passive"))
      (node (ref "U1") (pin "15") (pinfunction "SD3_15") (pintype "passive"))
    )
    (net (code "29") (name "/MUX2_SC0") (class "Default")
      (node (ref "J8") (pin "5") (pinfunction "5_5") (pintype "passive"))
      (node (ref "R38") (pin "2") (pinfunction "2_2") (pintype "passive"))
      (node (ref "U2") (pin "6") (pinfunction "SC0_6") (pintype "passive"))
    )
    (net (code "30") (name "/MUX2_SC1") (class "Default")
      (node (ref "J9") (pin "5") (pinfunction "5_5") (pintype "passive"))
      (node (ref "R40") (pin "2") (pinfunction "2_2") (pintype "passive"))
      (node (ref "U2") (pin "9") (pinfunction "SC1_9") (pintype "passive"))
    )
    (net (code "31") (name "/MUX2_SC2") (class "Default")
      (node (ref "J10") (pin "5") (pinfunction "5_5") (pintype "passive"))
      (node (ref "R42") (pin "2") (pinfunction "2_2") (pintype "passive"))
      (node (ref "U2") (pin "13") (pinfunction "SC2_13") (pintype "passive"))
      (node (ref "U8") (pin "4") (pinfunction "SCL/SPC_4") (pintype "input"))
    )
    (net (code "32") (name "/MUX2_SC3") (class "Default")
      (node (ref "J11") (pin "5") (pinfunction "5_5") (pintype "passive"))
      (node (ref "R44") (pin "2") (pinfunction "2_2") (pintype "passive"))
      (node (ref "U2") (pin "16") (pinfunction "SC3_16") (pintype "passive"))
    )
    (net (code "33") (name "/MUX2_SD0") (class "Default")
      (node (ref "J8") (pin "4") (pinfunction "4_4") (pintype "passive"))
      (node (ref "R37") (pin "2") (pinfunction "2_2") (pintype "passive"))
      (node (ref "U2") (pin "5") (pinfunction "SD0_5") (pintype "passive"))
    )
    (net (code "34") (name "/MUX2_SD1") (class "Default")
      (node (ref "J9") (pin "4") (pinfunction "4_4") (pintype "passive"))
      (node (ref "R39") (pin "2") (pinfunction "2_2") (pintype "passive"))
      (node (ref "U2") (pin "8") (pinfunction "SD1_8") (pintype "passive"))
    )
    (net (code "35") (name "/MUX2_SD2") (class "Default")
      (node (ref "J10") (pin "4") (pinfunction "4_4") (pintype "passive"))
      (node (ref "R41") (pin "2") (pinfunction "2_2") (pintype "passive"))
      (node (ref "U2") (pin "12") (pinfunction "SD2_12") (pintype "passive"))
      (node (ref "U8") (pin "6") (pinfunction "SDA/SDI/SDO_6") (pintype "bidirectional"))
    )
    (net (code "36") (name "/MUX2_SD3") (class "Default")
      (node (ref "J11") (pin "4") (pinfunction "4_4") (pintype "passive"))
      (node (ref "R43") (pin "2") (pinfunction "2_2") (pintype "passive"))
      (node (ref "U2") (pin "15") (pinfunction "SD3_15") (pintype "passive"))
    )
    (net (code "37") (name "/PGEC1") (class "Default")
      (node (ref "IC1") (pin "17") (pinfunction "PGEC1/OA1IN+/AN4/C1IN3-/C1IN1+/C2IN3-/RPI34/RB2_17") (pintype "bidirectional"))
      (node (ref "J12") (pin "5") (pinfunction "5_5") (pintype "passive"))
    )
    (net (code "38") (name "/PGED1") (class "Default")
      (node (ref "IC1") (pin "18") (pinfunction "PGED1/OA1IN-/AN5/C1IN1-/(CTMUC)/RP35/RTCC/RB3_18") (pintype "bidirectional"))
      (node (ref "J12") (pin "4") (pinfunction "4_4") (pintype "passive"))
    )
    (net (code "39") (name "/RGB_DIN") (class "Default")
      (node (ref "IC1") (pin "11") (pinfunction "AN10/RPI28/RA12_11") (pintype "bidirectional"))
      (node (ref "J13") (pin "3") (pinfunction "3_3") (pintype "passive"))
    )
    (net (code "40") (name "/SCK") (class "Default")
      (node (ref "IC1") (pin "35") (pinfunction "AN29/SCK1/RPI51/RC3_35") (pintype "bidirectional"))
      (node (ref "J4") (pin "4") (pinfunction "4_4") (pintype "passive"))
      (node (ref "U3") (pin "12") (pinfunction "B2_12") (pintype "bidirectional"))
    )
    (net (code "41") (name "/SCL1") (class "Default")
      (node (ref "IC1") (pin "37") (pinfunction "AN31/SCL1/RPI53/RC5_37") (pintype "bidirectional"))
      (node (ref "J1") (pin "5") (pinfunction "5_5") (pintype "passive"))
      (node (ref "R28") (pin "2") (pinfunction "2_2") (pintype "passive"))
      (node (ref "U1") (pin "18") (pinfunction "SCL_18") (pintype "passive"))
      (node (ref "U2") (pin "18") (pinfunction "SCL_18") (pintype "passive"))
    )
    (net (code "42") (name "/SDA1") (class "Default")
      (node (ref "IC1") (pin "36") (pinfunction "AN30/SDA1/RPI52/RC4_36") (pintype "bidirectional"))
      (node (ref "J1") (pin "4") (pinfunction "4_4") (pintype "passive"))
      (node (ref "R27") (pin "2") (pinfunction "2_2") (pintype "passive"))
      (node (ref "U1") (pin "19") (pinfunction "SDA_19") (pintype "passive"))
      (node (ref "U2") (pin "19") (pinfunction "SDA_19") (pintype "passive"))
    )
    (net (code "43") (name "/SD_MISO") (class "Default")
      (node (ref "J3") (pin "7") (pinfunction "DAT0_7") (pintype "bidirectional"))
      (node (ref "U3") (pin "5") (pinfunction "A4_5") (pintype "bidirectional"))
    )
    (net (code "44") (name "/SD_MOSI") (class "Default")
      (node (ref "J3") (pin "3") (pinfunction "CMD_3") (pintype "bidirectional"))
      (node (ref "U3") (pin "4") (pinfunction "A3_4") (pintype "bidirectional"))
    )
    (net (code "45") (name "/SD_SCK") (class "Default")
      (node (ref "J3") (pin "5") (pinfunction "CLK_5") (pintype "bidirectional"))
      (node (ref "U3") (pin "3") (pinfunction "A2_3") (pintype "bidirectional"))
    )
    (net (code "46") (name "/SD_~{SS}") (class "Default")
      (node (ref "J3") (pin "2") (pinfunction "CD/DAT3_2") (pintype "bidirectional"))
      (node (ref "U3") (pin "2") (pinfunction "A1_2") (pintype "bidirectional"))
    )
    (net (code "47") (name "/U1CTS") (class "Default")
      (node (ref "IC1") (pin "24") (pinfunction "AN11/C1IN2-/U1CTS/FLT4/PMA12/RC11_24") (pintype "bidirectional"))
      (node (ref "J14") (pin "2") (pinfunction "2_2") (pintype "passive"))
    )
    (net (code "48") (name "/U1RX") (class "Default")
      (node (ref "IC1") (pin "22") (pinfunction "OA3IN-/AN7/C3IN1-/C4IN1-/RP49/RC1_22") (pintype "bidirectional"))
      (node (ref "J14") (pin "4") (pinfunction "4_4") (pintype "passive"))
    )
    (net (code "49") (name "/U1TX") (class "Default")
      (node (ref "IC1") (pin "21") (pinfunction "OA3OUT/AN6/C3IN4-/C4IN1+/RP48/OCFB/RC0_21") (pintype "bidirectional"))
      (node (ref "J14") (pin "5") (pinfunction "5_5") (pintype "passive"))
    )
    (net (code "50") (name "/USBDM") (class "Default")
      (node (ref "R47") (pin "2") (pinfunction "2_2") (pintype "passive"))
    )
    (net (code "51") (name "/USBDP") (class "Default")
      (node (ref "R48") (pin "2") (pinfunction "2_2") (pintype "passive"))
    )
    (net (code "52") (name "/VBATT") (class "Default")
      (node (ref "C9") (pin "1") (pinfunction "1_1") (pintype "passive"))
      (node (ref "U4") (pin "5") (pinfunction "VIN_5") (pintype "power_in"))
    )
    (net (code "53") (name "/VCAP") (class "Default")
      (node (ref "C11") (pin "1") (pinfunction "1_1") (pintype "passive"))
      (node (ref "IC1") (pin "56") (pinfunction "VCAP_56") (pintype "bidirectional"))
    )
    (net (code "54") (name "/VCC_USB") (class "Default")
      (node (ref "C7") (pin "1") (pinfunction "1_1") (pintype "passive"))
      (node (ref "D9") (pin "A") (pinfunction "A_A") (pintype "passive"))
      (node (ref "J15") (pin "2") (pinfunction "2_2") (pintype "passive"))
      (node (ref "J17") (pin "1") (pinfunction "1_1") (pintype "bidirectional"))
      (node (ref "U5") (pin "4") (pinfunction "VDD_4") (pintype "passive"))
    )
    (net (code "55") (name "/VINA") (class "Default")
      (node (ref "U4") (pin "8") (pinfunction "VINA_8") (pintype "power_in"))
    )
    (net (code "56") (name "/V_BATT") (class "Default")
      (node (ref "C8") (pin "1") (pinfunction "1_1") (pintype "passive"))
      (node (ref "J16") (pin "2") (pinfunction "2_2") (pintype "passive"))
      (node (ref "U5") (pin "3") (pinfunction "VBAT_3") (pintype "passive"))
    )
    (net (code "57") (name "/~{MCLR}") (class "Default")
      (node (ref "IC1") (pin "7") (pinfunction "~{MCLR}_7") (pintype "bidirectional"))
      (node (ref "J12") (pin "1") (pinfunction "1_1") (pintype "passive"))
      (node (ref "R1") (pin "1") (pinfunction "1_1") (pintype "passive"))
    )
    (net (code "58") (name "/~{MUX1_INT0}") (class "Default")
      (node (ref "J2") (pin "3") (pinfunction "3_3") (pintype "passive"))
      (node (ref "U1") (pin "4") (pinfunction "~{INT0}_4") (pintype "passive"))
    )
    (net (code "59") (name "/~{MUX1_INT1}") (class "Default")
      (node (ref "J5") (pin "3") (pinfunction "3_3") (pintype "passive"))
      (node (ref "U1") (pin "7") (pinfunction "~{INT1}_7") (pintype "passive"))
    )
    (net (code "60") (name "/~{MUX1_INT2}") (class "Default")
      (node (ref "J6") (pin "3") (pinfunction "3_3") (pintype "passive"))
      (node (ref "U1") (pin "11") (pinfunction "~{INT2}_11") (pintype "passive"))
    )
    (net (code "61") (name "/~{MUX1_INT3}") (class "Default")
      (node (ref "J7") (pin "3") (pinfunction "3_3") (pintype "passive"))
      (node (ref "U1") (pin "14") (pinfunction "~{INT3}_14") (pintype "passive"))
    )
    (net (code "62") (name "/~{MUX2_INT0}") (class "Default")
      (node (ref "J8") (pin "3") (pinfunction "3_3") (pintype "passive"))
      (node (ref "U2") (pin "4") (pinfunction "~{INT0}_4") (pintype "passive"))
    )
    (net (code "63") (name "/~{MUX2_INT1}") (class "Default")
      (node (ref "J9") (pin "3") (pinfunction "3_3") (pintype "passive"))
      (node (ref "U2") (pin "7") (pinfunction "~{INT1}_7") (pintype "passive"))
    )
    (net (code "64") (name "/~{MUX2_INT2}") (class "Default")
      (node (ref "J10") (pin "3") (pinfunction "3_3") (pintype "passive"))
      (node (ref "U2") (pin "11") (pinfunction "~{INT2}_11") (pintype "passive"))
      (node (ref "U8") (pin "11") (pinfunction "INT_1_11") (pintype "output"))
    )
    (net (code "65") (name "/~{MUX2_INT3}") (class "Default")
      (node (ref "J11") (pin "3") (pinfunction "3_3") (pintype "passive"))
      (node (ref "U2") (pin "14") (pinfunction "~{INT3}_14") (pintype "passive"))
    )
    (net (code "66") (name "/~{SS}") (class "Default")
      (node (ref "IC1") (pin "15") (pinfunction "PGED3/VREF-/OA2IN-/AN2/C2IN1-/~{SS1}/RPI32/CTED2/RB0_15") (pintype "bidirectional"))
      (node (ref "J4") (pin "3") (pinfunction "3_3") (pintype "passive"))
      (node (ref "U3") (pin "13") (pinfunction "B1_13") (pintype "bidirectional"))
    )
    (net (code "67") (name "/~{U1RTS}") (class "Default")
      (node (ref "IC1") (pin "23") (pinfunction "OA3IN+/AN8/C3IN3-/C3IN1+/RPI50/~{U1RTS}/BCLK1/FLT3/RC2_23") (pintype "bidirectional"))
      (node (ref "J14") (pin "6") (pinfunction "6_6") (pintype "passive"))
    )
    (net (code "68") (name "GND") (class "Default")
      (node (ref "C1") (pin "2") (pinfunction "2_2") (pintype "passive"))
      (node (ref "C10") (pin "2") (pinfunction "2_2") (pintype "passive"))
      (node (ref "C11") (pin "2") (pinfunction "2_2") (pintype "passive"))
      (node (ref "C2") (pin "2") (pinfunction "2_2") (pintype "passive"))
      (node (ref "C3") (pin "2") (pinfunction "2_2") (pintype "passive"))
      (node (ref "C4") (pin "2") (pinfunction "2_2") (pintype "passive"))
      (node (ref "C5") (pin "2") (pinfunction "2_2") (pintype "passive"))
      (node (ref "C6") (pin "2") (pinfunction "2_2") (pintype "passive"))
      (node (ref "C7") (pin "2") (pinfunction "2_2") (pintype "passive"))
      (node (ref "C8") (pin "2") (pinfunction "2_2") (pintype "passive"))
      (node (ref "C9") (pin "2") (pinfunction "2_2") (pintype "passive"))
      (node (ref "D1") (pin "C") (pinfunction "C_C") (pintype "passive"))
      (node (ref "D2") (pin "C") (pinfunction "C_C") (pintype "passive"))
      (node (ref "D3") (pin "C") (pinfunction "C_C") (pintype "passive"))
      (node (ref "D4") (pin "C") (pinfunction "C_C") (pintype "passive"))
      (node (ref "D5") (pin "C") (pinfunction "C_C") (pintype "passive"))
      (node (ref "D6") (pin "C") (pinfunction "C_C") (pintype "passive"))
      (node (ref "D7") (pin "C") (pinfunction "C_C") (pintype "passive"))
      (node (ref "D8") (pin "C") (pinfunction "C_C") (pintype "passive"))
      (node (ref "H1") (pin "B3,0") (pinfunction "MOUNT_B3,0") (pintype "passive"))
      (node (ref "H2") (pin "B3,0") (pinfunction "MOUNT_B3,0") (pintype "passive"))
      (node (ref "H3") (pin "B3,0") (pinfunction "MOUNT_B3,0") (pintype "passive"))
      (node (ref "H4") (pin "B3,0") (pinfunction "MOUNT_B3,0") (pintype "passive"))
      (node (ref "IC1") (pin "20") (pinfunction "AVSS_20") (pintype "bidirectional"))
      (node (ref "IC1") (pin "26") (pinfunction "VDD_2_26") (pintype "bidirectional"))
      (node (ref "IC1") (pin "41") (pinfunction "VSS_3_41") (pintype "bidirectional"))
      (node (ref "IC1") (pin "9") (pinfunction "VSS_1_9") (pintype "bidirectional"))
      (node (ref "J1") (pin "2") (pinfunction "2_2") (pintype "passive"))
      (node (ref "J10") (pin "2") (pinfunction "2_2") (pintype "passive"))
      (node (ref "J11") (pin "2") (pinfunction "2_2") (pintype "passive"))
      (node (ref "J12") (pin "3") (pinfunction "3_3") (pintype "passive"))
      (node (ref "J13") (pin "1") (pinfunction "1_1") (pintype "passive"))
      (node (ref "J14") (pin "1") (pinfunction "1_1") (pintype "passive"))
      (node (ref "J15") (pin "1") (pinfunction "1_1") (pintype "passive"))
      (node (ref "J16") (pin "1") (pinfunction "1_1") (pintype "passive"))
      (node (ref "J17") (pin "5") (pinfunction "5_5") (pintype "bidirectional"))
      (node (ref "J17") (pin "P1") (pinfunction "P1_P1") (pintype "bidirectional"))
      (node (ref "J17") (pin "P2") (pinfunction "P2_P2") (pintype "bidirectional"))
      (node (ref "J17") (pin "P3") (pinfunction "P3_P3") (pintype "bidirectional"))
      (node (ref "J17") (pin "P4") (pinfunction "P4_P4") (pintype "bidirectional"))
      (node (ref "J17") (pin "P5") (pinfunction "P5_P5") (pintype "bidirectional"))
      (node (ref "J17") (pin "P6") (pinfunction "P6_P6") (pintype "bidirectional"))
      (node (ref "J2") (pin "2") (pinfunction "2_2") (pintype "passive"))
      (node (ref "J3") (pin "6") (pinfunction "VSS_6") (pintype "bidirectional"))
      (node (ref "J4") (pin "2") (pinfunction "2_2") (pintype "passive"))
      (node (ref "J5") (pin "2") (pinfunction "2_2") (pintype "passive"))
      (node (ref "J6") (pin "2") (pinfunction "2_2") (pintype "passive"))
      (node (ref "J7") (pin "2") (pinfunction "2_2") (pintype "passive"))
      (node (ref "J8") (pin "2") (pinfunction "2_2") (pintype "passive"))
      (node (ref "J9") (pin "2") (pinfunction "2_2") (pintype "passive"))
      (node (ref "R10") (pin "1") (pinfunction "1_1") (pintype "passive"))
      (node (ref "R12") (pin "1") (pinfunction "1_1") (pintype "passive"))
      (node (ref "R14") (pin "1") (pinfunction "1_1") (pintype "passive"))
      (node (ref "R16") (pin "1") (pinfunction "1_1") (pintype "passive"))
      (node (ref "R4") (pin "1") (pinfunction "1_1") (pintype "passive"))
      (node (ref "R46") (pin "1") (pinfunction "1_1") (pintype "passive"))
      (node (ref "R50") (pin "1") (pinfunction "1_1") (pintype "passive"))
      (node (ref "R6") (pin "1") (pinfunction "1_1") (pintype "passive"))
      (node (ref "R8") (pin "1") (pinfunction "1_1") (pintype "passive"))
      (node (ref "U1") (pin "10") (pinfunction "VSS_10") (pintype "passive"))
      (node (ref "U2") (pin "10") (pinfunction "VSS_10") (pintype "passive"))
      (node (ref "U3") (pin "7") (pinfunction "GND_7") (pintype "power_in"))
      (node (ref "U4") (pin "11") (pinfunction "EPAD_11") (pintype "passive"))
      (node (ref "U4") (pin "3") (pinfunction "PGND_3") (pintype "passive"))
      (node (ref "U4") (pin "9") (pinfunction "GND_9") (pintype "passive"))
      (node (ref "U5") (pin "2") (pinfunction "VSS_2") (pintype "passive"))
      (node (ref "U8") (pin "10") (pinfunction "GND_10") (pintype "power_in"))
      (node (ref "U8") (pin "12") (pinfunction "GND_12") (pintype "power_in"))
      (node (ref "U8") (pin "13") (pinfunction "GND_13") (pintype "power_in"))
      (node (ref "U8") (pin "16") (pinfunction "GND_16") (pintype "power_in"))
      (node (ref "U8") (pin "5") (pinfunction "GND_5") (pintype "power_in"))
    )
    (net (code "69") (name "Net-(D1-PadA)") (class "Default")
      (node (ref "D1") (pin "A") (pinfunction "A_A") (pintype "passive"))
      (node (ref "R17") (pin "1") (pinfunction "1_1") (pintype "passive"))
    )
    (net (code "70") (name "Net-(D2-PadA)") (class "Default")
      (node (ref "D2") (pin "A") (pinfunction "A_A") (pintype "passive"))
      (node (ref "R18") (pin "1") (pinfunction "1_1") (pintype "passive"))
    )
    (net (code "71") (name "Net-(D3-PadA)") (class "Default")
      (node (ref "D3") (pin "A") (pinfunction "A_A") (pintype "passive"))
      (node (ref "R19") (pin "1") (pinfunction "1_1") (pintype "passive"))
    )
    (net (code "72") (name "Net-(D4-PadA)") (class "Default")
      (node (ref "D4") (pin "A") (pinfunction "A_A") (pintype "passive"))
      (node (ref "R20") (pin "1") (pinfunction "1_1") (pintype "passive"))
    )
    (net (code "73") (name "Net-(D5-PadA)") (class "Default")
      (node (ref "D5") (pin "A") (pinfunction "A_A") (pintype "passive"))
      (node (ref "R21") (pin "1") (pinfunction "1_1") (pintype "passive"))
    )
    (net (code "74") (name "Net-(D6-PadA)") (class "Default")
      (node (ref "D6") (pin "A") (pinfunction "A_A") (pintype "passive"))
      (node (ref "R22") (pin "1") (pinfunction "1_1") (pintype "passive"))
    )
    (net (code "75") (name "Net-(D7-PadA)") (class "Default")
      (node (ref "D7") (pin "A") (pinfunction "A_A") (pintype "passive"))
      (node (ref "R23") (pin "1") (pinfunction "1_1") (pintype "passive"))
    )
    (net (code "76") (name "Net-(D8-PadA)") (class "Default")
      (node (ref "D8") (pin "A") (pinfunction "A_A") (pintype "passive"))
      (node (ref "R24") (pin "1") (pinfunction "1_1") (pintype "passive"))
    )
    (net (code "77") (name "Net-(D9-PadC)") (class "Default")
      (node (ref "D9") (pin "C") (pinfunction "C_C") (pintype "passive"))
      (node (ref "R45") (pin "1") (pinfunction "1_1") (pintype "passive"))
    )
    (net (code "78") (name "Net-(J3-DAT1)") (class "Default")
      (node (ref "J3") (pin "8") (pinfunction "DAT1_8") (pintype "bidirectional"))
      (node (ref "R26") (pin "2") (pinfunction "2_2") (pintype "passive"))
    )
    (net (code "79") (name "Net-(J3-DAT2)") (class "Default")
      (node (ref "J3") (pin "1") (pinfunction "DAT2_1") (pintype "bidirectional"))
      (node (ref "R25") (pin "2") (pinfunction "2_2") (pintype "passive"))
    )
    (net (code "80") (name "Net-(J17-Pad2)") (class "Default")
      (node (ref "J17") (pin "2") (pinfunction "2_2") (pintype "bidirectional"))
      (node (ref "R47") (pin "1") (pinfunction "1_1") (pintype "passive"))
    )
    (net (code "81") (name "Net-(J17-Pad3)") (class "Default")
      (node (ref "J17") (pin "3") (pinfunction "3_3") (pintype "bidirectional"))
      (node (ref "R48") (pin "1") (pinfunction "1_1") (pintype "passive"))
    )
    (net (code "82") (name "Net-(S1-1)") (class "Default")
      (node (ref "C1") (pin "1") (pinfunction "1_1") (pintype "passive"))
      (node (ref "S1") (pin "A2") (pinfunction "1_A2") (pintype "passive"))
    )
    (net (code "83") (name "Net-(S1-2)") (class "Default")
      (node (ref "R1") (pin "2") (pinfunction "2_2") (pintype "passive"))
      (node (ref "R2") (pin "2") (pinfunction "2_2") (pintype "passive"))
      (node (ref "S1") (pin "B2") (pinfunction "2_B2") (pintype "passive"))
    )
    (net (code "84") (name "Net-(U4-FB)") (class "Default")
      (node (ref "R49") (pin "1") (pinfunction "1_1") (pintype "passive"))
      (node (ref "R50") (pin "2") (pinfunction "2_2") (pintype "passive"))
      (node (ref "U4") (pin "10") (pinfunction "FB_10") (pintype "passive"))
    )
    (net (code "85") (name "Net-(U4-SW1)") (class "Default")
      (node (ref "U$1") (pin "2") (pinfunction "2_2") (pintype "passive"))
      (node (ref "U4") (pin "4") (pinfunction "SW1_4") (pintype "bidirectional"))
    )
    (net (code "86") (name "Net-(U4-SW2)") (class "Default")
      (node (ref "U$1") (pin "1") (pinfunction "1_1") (pintype "passive"))
      (node (ref "U4") (pin "2") (pinfunction "SW2_2") (pintype "bidirectional"))
    )
    (net (code "87") (name "Net-(U5-PROG)") (class "Default")
      (node (ref "R46") (pin "2") (pinfunction "2_2") (pintype "passive"))
      (node (ref "U5") (pin "5") (pinfunction "PROG_5") (pintype "passive"))
    )
    (net (code "88") (name "Net-(U5-STAT)") (class "Default")
      (node (ref "R45") (pin "2") (pinfunction "2_2") (pintype "passive"))
      (node (ref "U5") (pin "1") (pinfunction "STAT_1") (pintype "passive"))
    )
    (net (code "89") (name "unconnected-(IC1-AN9{slash}RPI27{slash}RA11-Pad12)") (class "Default")
      (node (ref "IC1") (pin "12") (pinfunction "AN9/RPI27/RA11_12") (pintype "bidirectional"))
    )
    (net (code "90") (name "unconnected-(IC1-AN12{slash}C2IN2-{slash}C5IN2-{slash}~{U2RTS}{slash}BCLK2{slash}FLT5{slash}PMA11{slash}RE12-Pad27)") (class "Default")
      (node (ref "IC1") (pin "27") (pinfunction "AN12/C2IN2-/C5IN2-/~{U2RTS}/BCLK2/FLT5/PMA11/RE12_27") (pintype "bidirectional"))
    )
    (net (code "91") (name "unconnected-(IC1-AN13{slash}C3IN2-{slash}~{U2CTS}{slash}FLT6{slash}PMA10{slash}RE13-Pad28)") (class "Default")
      (node (ref "IC1") (pin "28") (pinfunction "AN13/C3IN2-/~{U2CTS}/FLT6/PMA10/RE13_28") (pintype "bidirectional"))
    )
    (net (code "92") (name "unconnected-(IC1-AN14{slash}RPI94{slash}FLT7{slash}PMA1{slash}RE14-Pad29)") (class "Default")
      (node (ref "IC1") (pin "29") (pinfunction "AN14/RPI94/FLT7/PMA1/RE14_29") (pintype "bidirectional"))
    )
    (net (code "93") (name "unconnected-(IC1-AN15{slash}RPI95{slash}FLT8{slash}PMA0{slash}RE15-Pad30)") (class "Default")
      (node (ref "IC1") (pin "30") (pinfunction "AN15/RPI95/FLT8/PMA0/RE15_30") (pintype "bidirectional"))
    )
    (net (code "94") (name "unconnected-(IC1-AN16{slash}RPI121{slash}PMA2{slash}RG9-Pad8)") (class "Default")
      (node (ref "IC1") (pin "8") (pinfunction "AN16/RPI121/PMA2/RG9_8") (pintype "bidirectional"))
    )
    (net (code "95") (name "unconnected-(IC1-AN17{slash}ASDA1{slash}RP120{slash}PMA3{slash}RG8-Pad6)") (class "Default")
      (node (ref "IC1") (pin "6") (pinfunction "AN17/ASDA1/RP120/PMA3/RG8_6") (pintype "bidirectional"))
    )
    (net (code "96") (name "unconnected-(IC1-AN18{slash}ASCL1{slash}RPI119{slash}PMA4{slash}RG7-Pad5)") (class "Default")
      (node (ref "IC1") (pin "5") (pinfunction "AN18/ASCL1/RPI119/PMA4/RG7_5") (pintype "bidirectional"))
    )
    (net (code "97") (name "unconnected-(IC1-AN19{slash}RP118{slash}PMA5{slash}RG6-Pad4)") (class "Default")
      (node (ref "IC1") (pin "4") (pinfunction "AN19/RP118/PMA5/RG6_4") (pintype "bidirectional"))
    )
    (net (code "98") (name "unconnected-(IC1-AN48{slash}CVREF2O{slash}RPI58{slash}PMCS1{slash}RC10-Pad45)") (class "Default")
      (node (ref "IC1") (pin "45") (pinfunction "AN48/CVREF2O/RPI58/PMCS1/RC10_45") (pintype "bidirectional"))
    )
    (net (code "99") (name "unconnected-(IC1-AN49{slash}OSC1{slash}CLKI{slash}RPI60{slash}RC12-Pad39)") (class "Default")
      (node (ref "IC1") (pin "39") (pinfunction "AN49/OSC1/CLKI/RPI60/RC12_39") (pintype "bidirectional"))
    )
    (net (code "100") (name "unconnected-(IC1-FLT32{slash}SCL2{slash}RP36{slash}PMA8{slash}RB4-Pad32)") (class "Default")
      (node (ref "IC1") (pin "32") (pinfunction "FLT32/SCL2/RP36/PMA8/RB4_32") (pintype "bidirectional"))
    )
    (net (code "101") (name "unconnected-(IC1-OA2IN+{slash}AN1{slash}C2IN1+{slash}RPI17{slash}RA1-Pad14)") (class "Default")
      (node (ref "IC1") (pin "14") (pinfunction "OA2IN+/AN1/C2IN1+/RPI17/RA1_14") (pintype "bidirectional"))
    )
    (net (code "102") (name "unconnected-(IC1-OA2OUT{slash}AN0{slash}C2IN4-{slash}C4IN3-{slash}RPI16{slash}RA0-Pad13)") (class "Default")
      (node (ref "IC1") (pin "13") (pinfunction "OA2OUT/AN0/C2IN4-/C4IN3-/RPI16/RA0_13") (pintype "bidirectional"))
    )
    (net (code "103") (name "unconnected-(IC1-OA5OUT{slash}AN25{slash}C5IN4-{slash}RP39{slash}INT0{slash}RB7-Pad46)") (class "Default")
      (node (ref "IC1") (pin "46") (pinfunction "OA5OUT/AN25/C5IN4-/RP39/INT0/RB7_46") (pintype "bidirectional"))
    )
    (net (code "104") (name "unconnected-(IC1-OSC2{slash}CLKO{slash}RPI63{slash}RC15-Pad40)") (class "Default")
      (node (ref "IC1") (pin "40") (pinfunction "OSC2/CLKO/RPI63/RC15_40") (pintype "bidirectional"))
    )
    (net (code "105") (name "unconnected-(IC1-PGEC2{slash}ASCL2{slash}RP38{slash}PMCS2{slash}RB6-Pad44)") (class "Default")
      (node (ref "IC1") (pin "44") (pinfunction "PGEC2/ASCL2/RP38/PMCS2/RB6_44") (pintype "bidirectional"))
    )
    (net (code "106") (name "unconnected-(IC1-PGEC3{slash}VREF+{slash}CVREF+{slash}OA1OUT{slash}AN3{slash}C1IN4-{slash}C4IN2-{slash}RPI33{slash}CTED1{slash}RB1-Pad16)") (class "Default")
      (node (ref "IC1") (pin "16") (pinfunction "PGEC3/VREF+/CVREF+/OA1OUT/AN3/C1IN4-/C4IN2-/RPI33/CTED1/RB1_16") (pintype "bidirectional"))
    )
    (net (code "107") (name "unconnected-(IC1-PGED2{slash}ASDA2{slash}RP37{slash}RB5-Pad43)") (class "Default")
      (node (ref "IC1") (pin "43") (pinfunction "PGED2/ASDA2/RP37/RB5_43") (pintype "bidirectional"))
    )
    (net (code "108") (name "unconnected-(IC1-RP42{slash}PWM3H{slash}PMD0{slash}RB10-Pad60)") (class "Default")
      (node (ref "IC1") (pin "60") (pinfunction "RP42/PWM3H/PMD0/RB10_60") (pintype "bidirectional"))
    )
    (net (code "109") (name "unconnected-(IC1-RP43{slash}PWM3L{slash}PMD1{slash}RB11-Pad61)") (class "Default")
      (node (ref "IC1") (pin "61") (pinfunction "RP43/PWM3L/PMD1/RB11_61") (pintype "bidirectional"))
    )
    (net (code "110") (name "unconnected-(IC1-RP97{slash}RF1-Pad59)") (class "Default")
      (node (ref "IC1") (pin "59") (pinfunction "RP97/RF1_59") (pintype "bidirectional"))
    )
    (net (code "111") (name "unconnected-(IC1-RPI44{slash}PWM2H{slash}PMD2{slash}RB12-Pad62)") (class "Default")
      (node (ref "IC1") (pin "62") (pinfunction "RPI44/PWM2H/PMD2/RB12_62") (pintype "bidirectional"))
    )
    (net (code "112") (name "unconnected-(IC1-RPI45{slash}PWM2L{slash}CTPLS{slash}PMD3{slash}RB13-Pad63)") (class "Default")
      (node (ref "IC1") (pin "63") (pinfunction "RPI45/PWM2L/CTPLS/PMD3/RB13_63") (pintype "bidirectional"))
    )
    (net (code "113") (name "unconnected-(IC1-RPI46{slash}PWM1H{slash}T3CK{slash}T7CK{slash}PMD6{slash}RB14-Pad2)") (class "Default")
      (node (ref "IC1") (pin "2") (pinfunction "RPI46/PWM1H/T3CK/T7CK/PMD6/RB14_2") (pintype "bidirectional"))
    )
    (net (code "114") (name "unconnected-(IC1-RPI47{slash}PWM1L{slash}T5CK{slash}T6CK{slash}PMD7{slash}RB15-Pad3)") (class "Default")
      (node (ref "IC1") (pin "3") (pinfunction "RPI47/PWM1L/T5CK/T6CK/PMD7/RB15_3") (pintype "bidirectional"))
    )
    (net (code "115") (name "unconnected-(IC1-RPI72{slash}RD8-Pad42)") (class "Default")
      (node (ref "IC1") (pin "42") (pinfunction "RPI72/RD8_42") (pintype "bidirectional"))
    )
    (net (code "116") (name "unconnected-(IC1-RPI96{slash}RF0-Pad58)") (class "Default")
      (node (ref "IC1") (pin "58") (pinfunction "RPI96/RF0_58") (pintype "bidirectional"))
    )
    (net (code "117") (name "unconnected-(IC1-SDA2{slash}RPI24{slash}PMA9{slash}RA8-Pad31)") (class "Default")
      (node (ref "IC1") (pin "31") (pinfunction "SDA2/RPI24/PMA9/RA8_31") (pintype "bidirectional"))
    )
    (net (code "118") (name "unconnected-(IC1-SOSCI{slash}RPI61{slash}RC13-Pad47)") (class "Default")
      (node (ref "IC1") (pin "47") (pinfunction "SOSCI/RPI61/RC13_47") (pintype "bidirectional"))
    )
    (net (code "119") (name "unconnected-(IC1-TDI{slash}PWM4L{slash}PMD5{slash}RA7-Pad1)") (class "Default")
      (node (ref "IC1") (pin "1") (pinfunction "TDI/PWM4L/PMD5/RA7_1") (pintype "bidirectional"))
    )
    (net (code "120") (name "unconnected-(IC1-TDO{slash}PWM4H{slash}PMD4{slash}RA10-Pad64)") (class "Default")
      (node (ref "IC1") (pin "64") (pinfunction "TDO/PWM4H/PMD4/RA10_64") (pintype "bidirectional"))
    )
    (net (code "121") (name "unconnected-(J3-A-PadCD_A)") (class "Default")
      (node (ref "J3") (pin "CD_A") (pinfunction "A_CD_A") (pintype "bidirectional"))
    )
    (net (code "122") (name "unconnected-(J3-B-PadCD_B)") (class "Default")
      (node (ref "J3") (pin "CD_B") (pinfunction "B_CD_B") (pintype "bidirectional"))
    )
    (net (code "123") (name "unconnected-(J17-Pad4)") (class "Default")
      (node (ref "J17") (pin "4") (pinfunction "4_4") (pintype "bidirectional"))
    )
    (net (code "124") (name "unconnected-(U1-~{INT}-Pad17)") (class "Default")
      (node (ref "U1") (pin "17") (pinfunction "~{INT}_17") (pintype "passive"))
    )
    (net (code "125") (name "unconnected-(U2-~{INT}-Pad17)") (class "Default")
      (node (ref "U2") (pin "17") (pinfunction "~{INT}_17") (pintype "passive"))
    )
    (net (code "126") (name "unconnected-(U3-NC-Pad9)") (class "Default")
      (node (ref "U3") (pin "9") (pinfunction "NC_9") (pintype "passive"))
    )
    (net (code "127") (name "unconnected-(U3-NC_2-Pad6)") (class "Default")
      (node (ref "U3") (pin "6") (pinfunction "NC_2_6") (pintype "passive"))
    )
    (net (code "128") (name "unconnected-(U3-OE-Pad8)") (class "Default")
      (node (ref "U3") (pin "8") (pinfunction "OE_8") (pintype "output"))
    )
    (net (code "129") (name "unconnected-(U4-EN-Pad6)") (class "Default")
      (node (ref "U4") (pin "6") (pinfunction "EN_6") (pintype "passive"))
    )
    (net (code "130") (name "unconnected-(U4-MODE{slash}SYNC-Pad7)") (class "Default")
      (node (ref "U4") (pin "7") (pinfunction "MODE/SYNC_7") (pintype "passive"))
    )
    (net (code "131") (name "unconnected-(U8-CS-Pad8)") (class "Default")
      (node (ref "U8") (pin "8") (pinfunction "CS_8") (pintype "input"))
    )
  )
)
